# SilentStepStick-TMC2130_v20.net
KiCad netlist of a schematic drawn in EAGLE
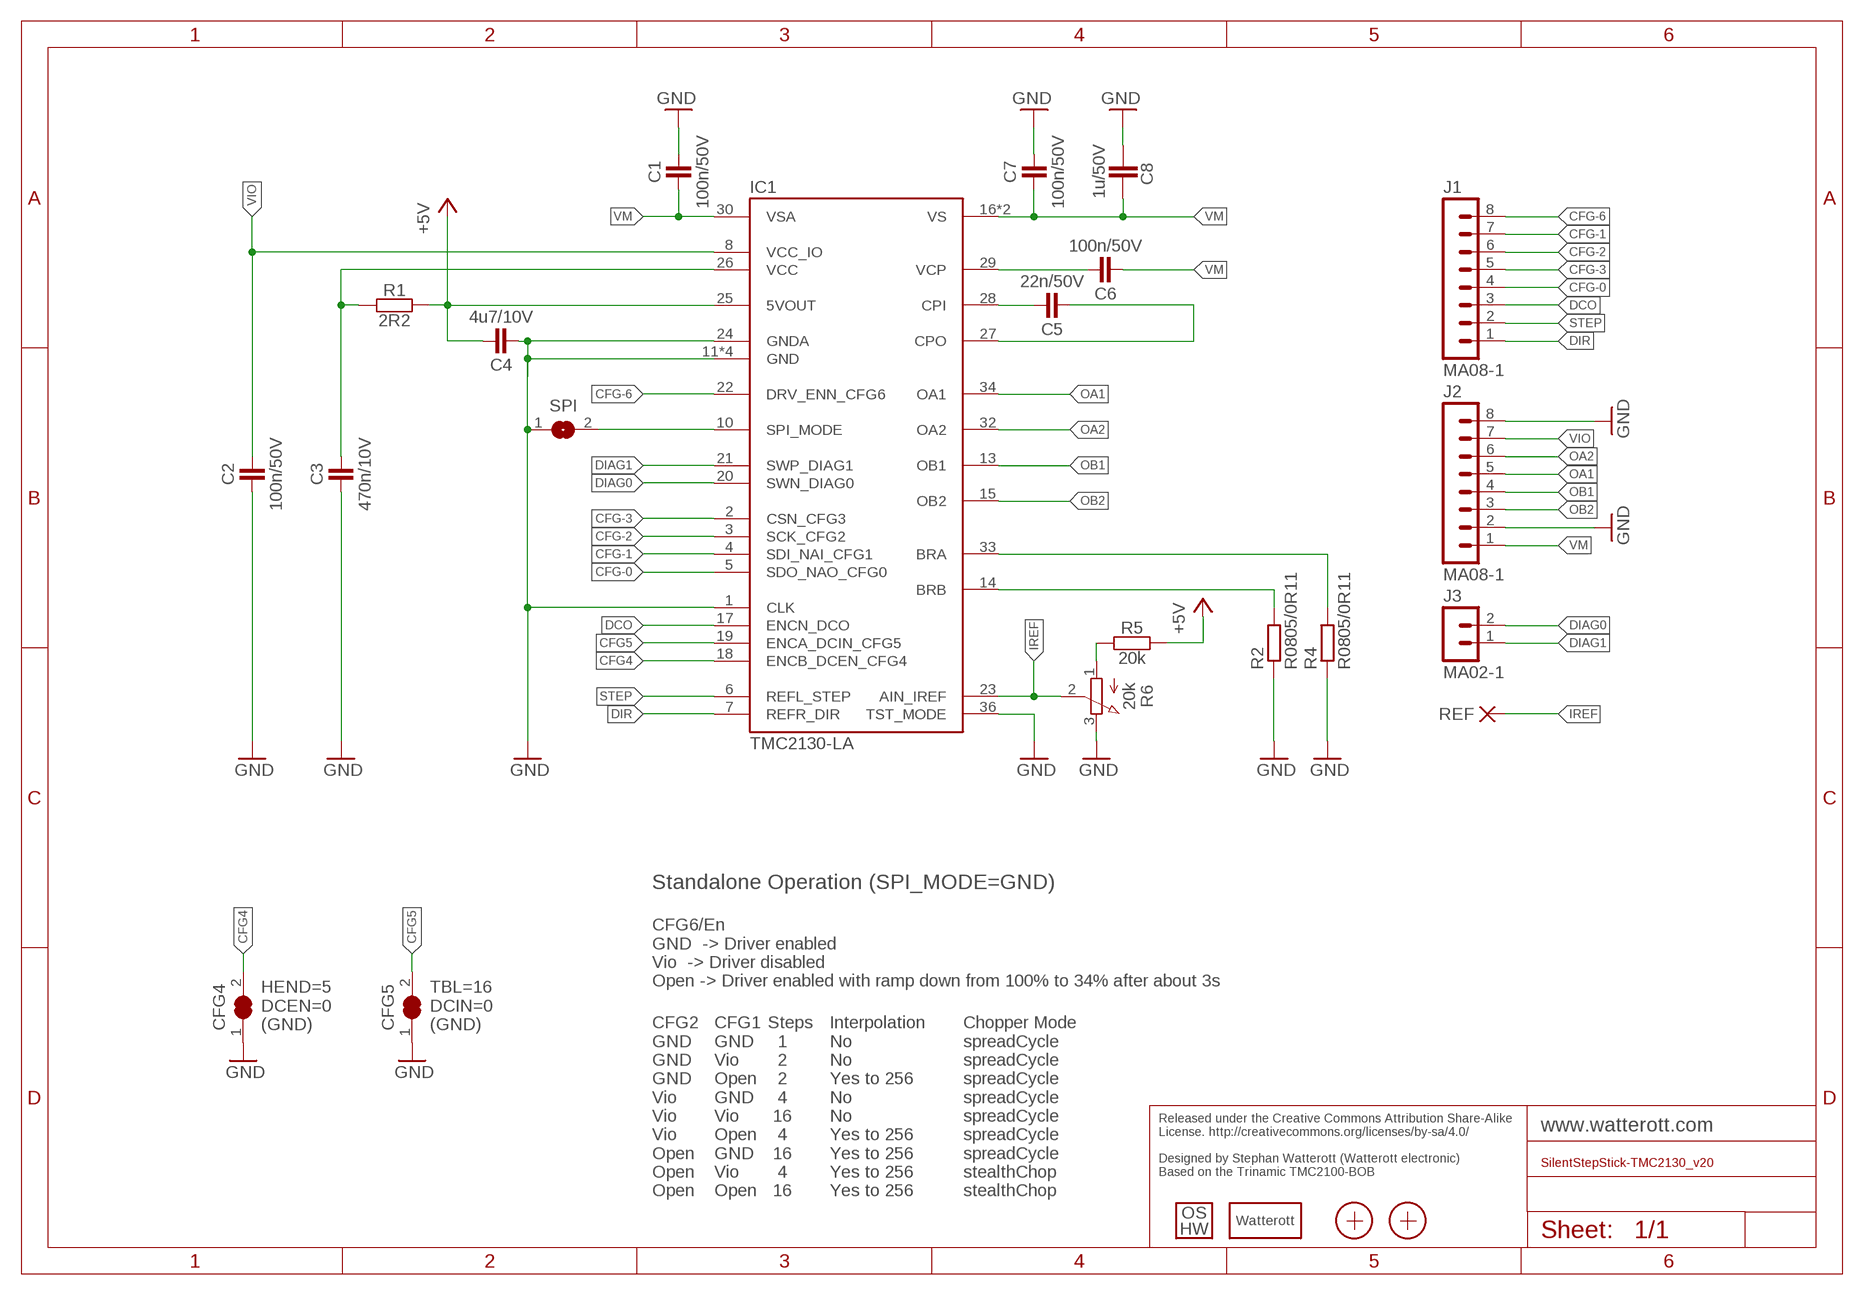
[diagram p0: schematic, sheet 1]

(export (version "E")
  (design (tool "Eeschema 10.0.6"))
  (components
    (comp (ref "C1")
      (value "100n/50V")
      (footprint "eagle-import:C0402")
      (libsource (lib "eagle-import") (part "CAPACITOR-0402"))
    )
    (comp (ref "C2")
      (value "100n/50V")
      (footprint "eagle-import:C0402")
      (libsource (lib "eagle-import") (part "CAPACITOR-0402"))
    )
    (comp (ref "C3")
      (value "470n/10V")
      (footprint "eagle-import:C0402")
      (libsource (lib "eagle-import") (part "CAPACITOR-0402"))
    )
    (comp (ref "C4")
      (value "4u7/10V")
      (footprint "eagle-import:C0402")
      (libsource (lib "eagle-import") (part "CAPACITOR-0402"))
    )
    (comp (ref "C5")
      (value "22n/50V")
      (footprint "eagle-import:C0402")
      (libsource (lib "eagle-import") (part "CAPACITOR-0402"))
    )
    (comp (ref "C6")
      (value "100n/50V")
      (footprint "eagle-import:C0402")
      (libsource (lib "eagle-import") (part "CAPACITOR-0402"))
    )
    (comp (ref "C7")
      (value "100n/50V")
      (footprint "eagle-import:C0402")
      (libsource (lib "eagle-import") (part "CAPACITOR-0402"))
    )
    (comp (ref "C8")
      (value "1u/50V")
      (footprint "eagle-import:C0603")
      (libsource (lib "eagle-import") (part "C-EUC0603"))
    )
    (comp (ref "CFG4")
      (value "JUMPER2-0201")
      (footprint "eagle-import:JUMPER2-0201")
      (libsource (lib "eagle-import") (part "JUMPER2-0201"))
    )
    (comp (ref "CFG5")
      (value "JUMPER2-0201")
      (footprint "eagle-import:JUMPER2-0201")
      (libsource (lib "eagle-import") (part "JUMPER2-0201"))
    )
    (comp (ref "IC1")
      (value "TMC2130-LA")
      (footprint "eagle-import:QFN36-PAD")
      (libsource (lib "eagle-import") (part "TMC21X0-LA"))
    )
    (comp (ref "J1")
      (value "MA08-1")
      (footprint "eagle-import:MA08-1")
      (libsource (lib "eagle-import") (part "MA08-1"))
    )
    (comp (ref "J2")
      (value "MA08-1")
      (footprint "eagle-import:MA08-1")
      (libsource (lib "eagle-import") (part "MA08-1"))
    )
    (comp (ref "J3")
      (value "MA02-1")
      (footprint "eagle-import:MA02-1")
      (libsource (lib "eagle-import") (part "MA02-1"))
    )
    (comp (ref "LOGO3")
      (value "LOGO_SPARK-2")
      (footprint "eagle-import:SPARK_2MM")
      (libsource (lib "eagle-import") (part "LOGO_SPARK-2"))
    )
    (comp (ref "LOGO4")
      (value "LOGO_OSHW-2")
      (footprint "eagle-import:OSHW_2MM")
      (libsource (lib "eagle-import") (part "LOGO_OSHW-2"))
    )
    (comp (ref "R1")
      (value "2R2")
      (footprint "eagle-import:C0402")
      (libsource (lib "eagle-import") (part "RESISTOR-0402"))
    )
    (comp (ref "R2")
      (value "R0805/0R11")
      (footprint "eagle-import:M0805")
      (libsource (lib "eagle-import") (part "R-EU_M0805"))
    )
    (comp (ref "R4")
      (value "R0805/0R11")
      (footprint "eagle-import:M0805")
      (libsource (lib "eagle-import") (part "R-EU_M0805"))
    )
    (comp (ref "R5")
      (value "20k")
      (footprint "eagle-import:C0402")
      (libsource (lib "eagle-import") (part "RESISTOR-0402"))
    )
    (comp (ref "R6")
      (value "20k")
      (footprint "eagle-import:POT_EVM3R")
      (libsource (lib "eagle-import") (part "POT-EVM3R"))
    )
    (comp (ref "REF")
      (value "PAD-0.6-1.1")
      (footprint "eagle-import:PAD-0.6-1.1")
      (libsource (lib "eagle-import") (part "PAD-0.6-1.1"))
    )
    (comp (ref "SPI")
      (value "JUMPER2-0402-NC")
      (footprint "eagle-import:JUMPER2-0402_NC")
      (libsource (lib "eagle-import") (part "JUMPER2-0402-NC"))
    )
    (comp (ref "X1")
      (value "PASSER-07")
      (footprint "eagle-import:PASSER_07MM")
      (libsource (lib "eagle-import") (part "PASSER-07"))
    )
    (comp (ref "X2")
      (value "PASSER-07")
      (footprint "eagle-import:PASSER_07MM")
      (libsource (lib "eagle-import") (part "PASSER-07"))
    )
  )
  (nets
    (net (code "1") (name "+5V") (class "Default")
      (node (ref "C4") (pin "2") (pinfunction "2_2") (pintype "passive"))
      (node (ref "IC1") (pin "25") (pinfunction "5VOUT_25") (pintype "power_in"))
      (node (ref "R1") (pin "2") (pinfunction "2_2") (pintype "passive"))
      (node (ref "R5") (pin "2") (pinfunction "2_2") (pintype "passive"))
    )
    (net (code "2") (name "CFG-0") (class "Default")
      (node (ref "IC1") (pin "5") (pinfunction "SDO_NAO_CFG0_5") (pintype "bidirectional"))
      (node (ref "J1") (pin "4") (pinfunction "4_4") (pintype "passive"))
    )
    (net (code "3") (name "CFG-1") (class "Default")
      (node (ref "IC1") (pin "4") (pinfunction "SDI_NAI_CFG1_4") (pintype "bidirectional"))
      (node (ref "J1") (pin "7") (pinfunction "7_7") (pintype "passive"))
    )
    (net (code "4") (name "CFG-2") (class "Default")
      (node (ref "IC1") (pin "3") (pinfunction "SCK_CFG2_3") (pintype "bidirectional"))
      (node (ref "J1") (pin "6") (pinfunction "6_6") (pintype "passive"))
    )
    (net (code "5") (name "CFG-3") (class "Default")
      (node (ref "IC1") (pin "2") (pinfunction "CSN_CFG3_2") (pintype "bidirectional"))
      (node (ref "J1") (pin "5") (pinfunction "5_5") (pintype "passive"))
    )
    (net (code "6") (name "CFG-6") (class "Default")
      (node (ref "IC1") (pin "22") (pinfunction "DRV_ENN_CFG6_22") (pintype "bidirectional"))
      (node (ref "J1") (pin "8") (pinfunction "8_8") (pintype "passive"))
    )
    (net (code "7") (name "CFG4") (class "Default")
      (node (ref "CFG4") (pin "2") (pinfunction "2_2") (pintype "passive"))
      (node (ref "IC1") (pin "18") (pinfunction "ENCB_DCEN_CFG4_18") (pintype "bidirectional"))
    )
    (net (code "8") (name "CFG5") (class "Default")
      (node (ref "CFG5") (pin "2") (pinfunction "2_2") (pintype "passive"))
      (node (ref "IC1") (pin "19") (pinfunction "ENCA_DCIN_CFG5_19") (pintype "bidirectional"))
    )
    (net (code "9") (name "DCO") (class "Default")
      (node (ref "IC1") (pin "17") (pinfunction "ENCN_DCO_17") (pintype "bidirectional"))
      (node (ref "J1") (pin "3") (pinfunction "3_3") (pintype "passive"))
    )
    (net (code "10") (name "DIAG0") (class "Default")
      (node (ref "IC1") (pin "20") (pinfunction "SWN_DIAG0_20") (pintype "bidirectional"))
      (node (ref "J3") (pin "2") (pinfunction "2_2") (pintype "passive"))
    )
    (net (code "11") (name "DIAG1") (class "Default")
      (node (ref "IC1") (pin "21") (pinfunction "SWP_DIAG1_21") (pintype "bidirectional"))
      (node (ref "J3") (pin "1") (pinfunction "1_1") (pintype "passive"))
    )
    (net (code "12") (name "DIR") (class "Default")
      (node (ref "IC1") (pin "7") (pinfunction "REFR_DIR_7") (pintype "bidirectional"))
      (node (ref "J1") (pin "1") (pinfunction "1_1") (pintype "passive"))
    )
    (net (code "13") (name "GND") (class "Default")
      (node (ref "C1") (pin "2") (pinfunction "2_2") (pintype "passive"))
      (node (ref "C2") (pin "1") (pinfunction "1_1") (pintype "passive"))
      (node (ref "C3") (pin "1") (pinfunction "1_1") (pintype "passive"))
      (node (ref "C4") (pin "1") (pinfunction "1_1") (pintype "passive"))
      (node (ref "C7") (pin "2") (pinfunction "2_2") (pintype "passive"))
      (node (ref "C8") (pin "2") (pinfunction "2_2") (pintype "passive"))
      (node (ref "CFG4") (pin "1") (pinfunction "1_1") (pintype "passive"))
      (node (ref "CFG5") (pin "1") (pinfunction "1_1") (pintype "passive"))
      (node (ref "IC1") (pin "1") (pinfunction "CLK_1") (pintype "bidirectional"))
      (node (ref "IC1") (pin "11") (pinfunction "GND_11") (pintype "power_in"))
      (node (ref "IC1") (pin "12") (pinfunction "GND_12") (pintype "power_in"))
      (node (ref "IC1") (pin "24") (pinfunction "GNDA_24") (pintype "power_in"))
      (node (ref "IC1") (pin "35") (pinfunction "GND_35") (pintype "power_in"))
      (node (ref "IC1") (pin "36") (pinfunction "TST_MODE_36") (pintype "bidirectional"))
      (node (ref "IC1") (pin "TP") (pinfunction "GND_TP") (pintype "power_in"))
      (node (ref "J2") (pin "2") (pinfunction "2_2") (pintype "passive"))
      (node (ref "J2") (pin "8") (pinfunction "8_8") (pintype "passive"))
      (node (ref "R2") (pin "1") (pinfunction "1_1") (pintype "passive"))
      (node (ref "R4") (pin "1") (pinfunction "1_1") (pintype "passive"))
      (node (ref "R6") (pin "3") (pinfunction "E_3") (pintype "passive"))
      (node (ref "SPI") (pin "1") (pinfunction "1_1") (pintype "passive"))
    )
    (net (code "14") (name "IREF") (class "Default")
      (node (ref "IC1") (pin "23") (pinfunction "AIN_IREF_23") (pintype "passive"))
      (node (ref "R6") (pin "2") (pinfunction "S_2") (pintype "passive"))
      (node (ref "REF") (pin "1") (pinfunction "P_1") (pintype "passive"))
    )
    (net (code "15") (name "Net-(IC1-BRA)") (class "Default")
      (node (ref "IC1") (pin "33") (pinfunction "BRA_33") (pintype "output"))
      (node (ref "R4") (pin "2") (pinfunction "2_2") (pintype "passive"))
    )
    (net (code "16") (name "Net-(IC1-BRB)") (class "Default")
      (node (ref "IC1") (pin "14") (pinfunction "BRB_14") (pintype "output"))
      (node (ref "R2") (pin "2") (pinfunction "2_2") (pintype "passive"))
    )
    (net (code "17") (name "Net-(IC1-CPI)") (class "Default")
      (node (ref "C5") (pin "2") (pinfunction "2_2") (pintype "passive"))
      (node (ref "IC1") (pin "28") (pinfunction "CPI_28") (pintype "passive"))
    )
    (net (code "18") (name "Net-(IC1-CPO)") (class "Default")
      (node (ref "C5") (pin "1") (pinfunction "1_1") (pintype "passive"))
      (node (ref "IC1") (pin "27") (pinfunction "CPO_27") (pintype "passive"))
    )
    (net (code "19") (name "Net-(IC1-SPI_MODE)") (class "Default")
      (node (ref "IC1") (pin "10") (pinfunction "SPI_MODE_10") (pintype "bidirectional"))
      (node (ref "SPI") (pin "2") (pinfunction "2_2") (pintype "passive"))
    )
    (net (code "20") (name "Net-(IC1-VCC)") (class "Default")
      (node (ref "C3") (pin "2") (pinfunction "2_2") (pintype "passive"))
      (node (ref "IC1") (pin "26") (pinfunction "VCC_26") (pintype "power_in"))
      (node (ref "R1") (pin "1") (pinfunction "1_1") (pintype "passive"))
    )
    (net (code "21") (name "Net-(IC1-VCP)") (class "Default")
      (node (ref "C6") (pin "2") (pinfunction "2_2") (pintype "passive"))
      (node (ref "IC1") (pin "29") (pinfunction "VCP_29") (pintype "passive"))
    )
    (net (code "22") (name "Net-(R6-A)") (class "Default")
      (node (ref "R5") (pin "1") (pinfunction "1_1") (pintype "passive"))
      (node (ref "R6") (pin "1") (pinfunction "A_1") (pintype "passive"))
    )
    (net (code "23") (name "OA1") (class "Default")
      (node (ref "IC1") (pin "34") (pinfunction "OA1_34") (pintype "output"))
      (node (ref "J2") (pin "5") (pinfunction "5_5") (pintype "passive"))
    )
    (net (code "24") (name "OA2") (class "Default")
      (node (ref "IC1") (pin "32") (pinfunction "OA2_32") (pintype "output"))
      (node (ref "J2") (pin "6") (pinfunction "6_6") (pintype "passive"))
    )
    (net (code "25") (name "OB1") (class "Default")
      (node (ref "IC1") (pin "13") (pinfunction "OB1_13") (pintype "output"))
      (node (ref "J2") (pin "4") (pinfunction "4_4") (pintype "passive"))
    )
    (net (code "26") (name "OB2") (class "Default")
      (node (ref "IC1") (pin "15") (pinfunction "OB2_15") (pintype "output"))
      (node (ref "J2") (pin "3") (pinfunction "3_3") (pintype "passive"))
    )
    (net (code "27") (name "STEP") (class "Default")
      (node (ref "IC1") (pin "6") (pinfunction "REFL_STEP_6") (pintype "bidirectional"))
      (node (ref "J1") (pin "2") (pinfunction "2_2") (pintype "passive"))
    )
    (net (code "28") (name "VIO") (class "Default")
      (node (ref "C2") (pin "2") (pinfunction "2_2") (pintype "passive"))
      (node (ref "IC1") (pin "8") (pinfunction "VCC_IO_8") (pintype "power_in"))
      (node (ref "J2") (pin "7") (pinfunction "7_7") (pintype "passive"))
    )
    (net (code "29") (name "VM") (class "Default")
      (node (ref "C1") (pin "1") (pinfunction "1_1") (pintype "passive"))
      (node (ref "C6") (pin "1") (pinfunction "1_1") (pintype "passive"))
      (node (ref "C7") (pin "1") (pinfunction "1_1") (pintype "passive"))
      (node (ref "C8") (pin "1") (pinfunction "1_1") (pintype "passive"))
      (node (ref "IC1") (pin "16") (pinfunction "VS_16") (pintype "power_in"))
      (node (ref "IC1") (pin "30") (pinfunction "VSA_30") (pintype "power_in"))
      (node (ref "IC1") (pin "31") (pinfunction "VS_31") (pintype "power_in"))
      (node (ref "J2") (pin "1") (pinfunction "1_1") (pintype "passive"))
    )
  )
)
